# 07_-_Motor.net
KiCad netlist of a schematic drawn in Altium Designer
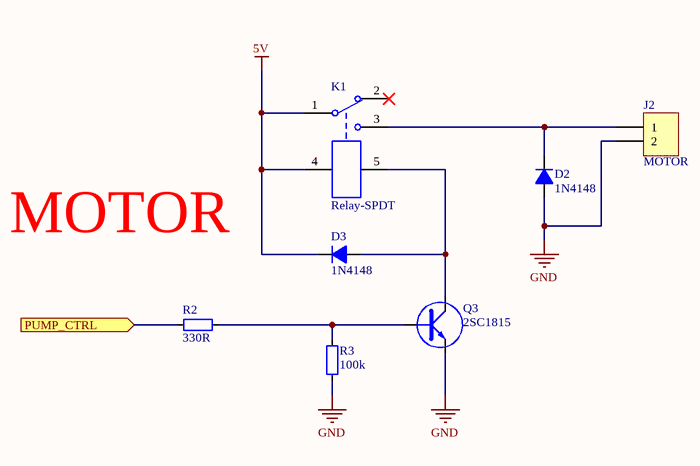
[diagram p0: [07] - Motor.SchDoc]

(export (version "E")
  (design (tool "Eeschema 10.0.6"))
  (components
    (comp (ref "D2")
      (value "1N4148")
      (footprint "1N4148_SMD")
      (description "Diode 1A")
      (libsource (lib "My Library") (part "D1A"))
    )
    (comp (ref "D3")
      (value "1N4148")
      (footprint "1N4148_SMD")
      (description "Diode 1A")
      (libsource (lib "My Library") (part "D1A"))
    )
    (comp (ref "J2")
      (value "MOTOR")
      (footprint "KF2-5.08")
      (fields
        (field (name "MANUFACTURER") "Würth Elektronik eiSos GmbH")
        (field (name "PARTNO") "691103110002")
        (field (name "CREATED BY") "Karrer Zheng")
      )
      (libsource (lib "My Library") (part "KF2"))
    )
    (comp (ref "K1")
      (value "Relay-SPDT")
      (footprint "RELAY5PIN-10A")
      (description "Single-Pole Dual-Throw Relay")
      (fields (field (name "PUBLISHER") "Altium Limited"))
      (libsource (lib "My Library") (part "Relay-SPDT"))
    )
    (comp (ref "Q3")
      (value "2SC1815")
      (footprint "SOT23")
      (description "NPN 600mW, ECB")
      (libsource (lib "My Library") (part "2SC1815"))
    )
    (comp (ref "R2")
      (value "330R")
      (footprint "RES-SMD-0805")
      (description "Resistor")
      (fields
        (field (name "MANUFACTURER") "Generic Components")
        (field (name "PUBLISHER") "Altium Hobart Technology Centre")
      )
      (libsource (lib "My Library") (part "Resistor - SMD"))
    )
    (comp (ref "R3")
      (value "100k")
      (footprint "RES-SMD-0805")
      (description "Resistor")
      (fields
        (field (name "MANUFACTURER") "Generic Components")
        (field (name "PUBLISHER") "Altium Hobart Technology Centre")
      )
      (libsource (lib "My Library") (part "Resistor - SMD"))
    )
  )
  (nets
    (net (code "1") (name "/PUMP_CTRL") (class "Default")
      (node (ref "R2") (pin "1") (pinfunction "1_1") (pintype "passive"))
    )
    (net (code "2") (name "5V") (class "Default")
      (node (ref "D3") (pin "2") (pinfunction "K_2") (pintype "passive"))
      (node (ref "K1") (pin "1") (pinfunction "1_1") (pintype "passive"))
      (node (ref "K1") (pin "4") (pinfunction "4_4") (pintype "passive"))
    )
    (net (code "3") (name "GND") (class "Default")
      (node (ref "D2") (pin "1") (pinfunction "A_1") (pintype "passive"))
      (node (ref "J2") (pin "2") (pinfunction "2_2") (pintype "passive"))
      (node (ref "Q3") (pin "3") (pinfunction "E_3") (pintype "passive"))
      (node (ref "R3") (pin "1") (pinfunction "1_1") (pintype "passive"))
    )
    (net (code "4") (name "Net-(D2-K)") (class "Default")
      (node (ref "D2") (pin "2") (pinfunction "K_2") (pintype "passive"))
      (node (ref "J2") (pin "1") (pinfunction "1_1") (pintype "passive"))
      (node (ref "K1") (pin "3") (pinfunction "3_3") (pintype "passive"))
    )
    (net (code "5") (name "Net-(D3-A)") (class "Default")
      (node (ref "D3") (pin "1") (pinfunction "A_1") (pintype "passive"))
      (node (ref "K1") (pin "5") (pinfunction "5_5") (pintype "passive"))
      (node (ref "Q3") (pin "2") (pinfunction "C_2") (pintype "passive"))
    )
    (net (code "6") (name "Net-(Q3-B)") (class "Default")
      (node (ref "Q3") (pin "1") (pinfunction "B_1") (pintype "passive"))
      (node (ref "R2") (pin "2") (pinfunction "2_2") (pintype "passive"))
      (node (ref "R3") (pin "2") (pinfunction "2_2") (pintype "passive"))
    )
    (net (code "7") (name "unconnected-(K1-Pad2)") (class "Default")
      (node (ref "K1") (pin "2") (pinfunction "2_2") (pintype "passive+no_connect"))
    )
  )
)
